# GPSDO_GPS.net
KiCad netlist of a schematic drawn in Altium Designer
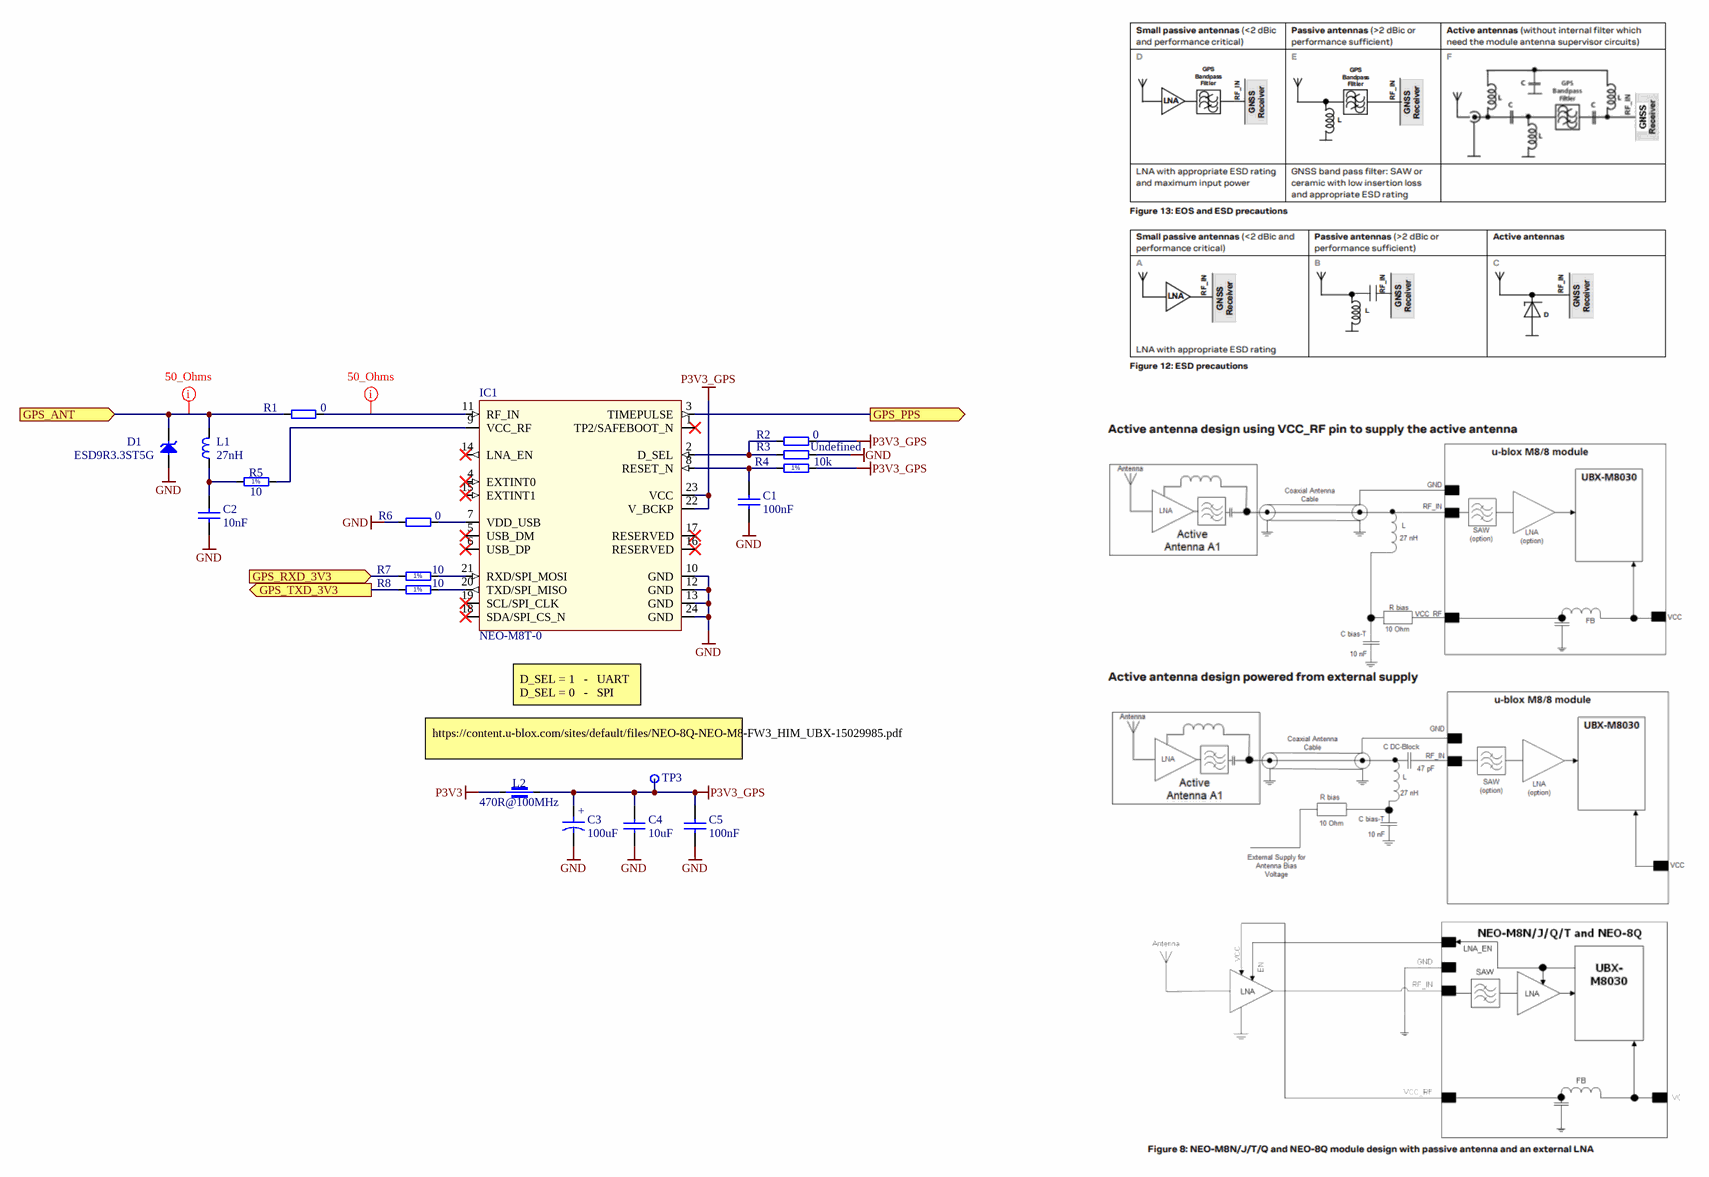
[diagram p0: GPSDO_GPS.SchDoc]

(export (version "E")
  (design (tool "Eeschema 10.0.6"))
  (components
    (comp (ref "C1")
      (value "100nF")
      (footprint "CAPC1005X55N")
      (description "Non-polarised capacitor")
      (fields
        (field (name "PART NUMBER") "CC0402_100NF_16V_10%_X5R")
        (field (name "VOLTAGE") "16V")
        (field (name "AUTHOR") "CERN DEM JLC")
      )
      (libsource (lib "Capacitors") (part "Capacitor - non polarized"))
    )
    (comp (ref "C2")
      (value "10nF")
      (footprint "CAPC1005X55N")
      (description "Non-polarised capacitor")
      (fields
        (field (name "PART NUMBER") "CC0402_10NF_50V_10%_X7R")
        (field (name "VOLTAGE") "50V")
        (field (name "AUTHOR") "CERN DEM MR")
      )
      (libsource (lib "Capacitors") (part "Capacitor - non polarized"))
    )
    (comp (ref "C3")
      (value "100uF")
      (footprint "CAPMP7343X310N")
      (description "Polarised capacitor")
      (fields
        (field (name "PART NUMBER") "CTE7343-31_100UF_20V_10%")
        (field (name "VOLTAGE") "20V")
        (field (name "AUTHOR") "CERN DEM JLC")
      )
      (libsource (lib "Capacitors") (part "Capacitor - polarized"))
    )
    (comp (ref "C4")
      (value "10uF")
      (footprint "CAPC1608X80N")
      (description "Non-polarised capacitor")
      (fields
        (field (name "PART NUMBER") "CC0603_10UF_10V_10%_X5R")
        (field (name "VOLTAGE") "10V")
        (field (name "AUTHOR") "CERN DEM JLC")
      )
      (libsource (lib "Capacitors") (part "Capacitor - non polarized"))
    )
    (comp (ref "C5")
      (value "100nF")
      (footprint "CAPC1005X55N")
      (description "Non-polarised capacitor")
      (fields
        (field (name "PART NUMBER") "CC0402_100NF_16V_10%_X5R")
        (field (name "VOLTAGE") "16V")
        (field (name "AUTHOR") "CERN DEM JLC")
      )
      (libsource (lib "Capacitors") (part "Capacitor - non polarized"))
    )
    (comp (ref "D1")
      (value "ESD9R3.3ST5G")
      (footprint "SOD923")
      (description "Transient Voltage Suppressor Diode (Uni-Directional)")
      (fields (field (name "MANUFACTURER") "ONSEMI"))
      (libsource (lib "Lib") (part "ESD9R3.3ST5G"))
    )
    (comp (ref "IC1")
      (value "NEO-M8T-0")
      (footprint "NEO-M8T_UBL")
      (description "No Description Available")
      (fields (field (name "MANUFACTURER") "Ublox"))
      (libsource (lib "NEO-M8T-0") (part "NEO-M8T-0"))
    )
    (comp (ref "L1")
      (value "27nH")
      (footprint "INDC0402X60N")
      (description "SMD Inductor")
      (fields
        (field (name "MANUFACTURER") "Murata")
        (field (name "MANUFACTURER PART NUMBER") "LQG15HS27NH02D")
      )
      (libsource (lib "Lib") (part "IND_27NH"))
    )
    (comp (ref "L2")
      (value "470R@100MHz")
      (footprint "INDC1608X95N")
      (fields
        (field (name "PART NUMBER") "IND0603_MURATA_BLM18PG471SN1D")
        (field (name "POWER") "1A")
        (field (name "TOLERANCE") "±25%")
        (field (name "AUTHOR") "CERN DEM BC")
      )
      (libsource (lib "Inductors & Transformers") (part "Ferrite Bead"))
    )
    (comp (ref "R1")
      (value "0")
      (footprint "RESC1005X40N")
      (description "Resistor")
      (fields
        (field (name "PART NUMBER") "R0402_0R_JUMPER")
        (field (name "MANUFACTURER") "GENERIC")
        (field (name "AUTHOR") "CERN DEM JLC")
      )
      (libsource (lib "Resistors") (part "Resistor"))
    )
    (comp (ref "R2")
      (value "0")
      (footprint "RESC1005X40N")
      (description "Resistor")
      (fields
        (field (name "PART NUMBER") "R0402_0R_JUMPER")
        (field (name "MANUFACTURER") "GENERIC")
        (field (name "AUTHOR") "CERN DEM JLC")
      )
      (libsource (lib "Resistors") (part "Resistor"))
    )
    (comp (ref "R3")
      (value "Undefined")
      (footprint "RESC1005X40N")
      (description "Resistor")
      (fields (field (name "PART NUMBER") "R0402_NO-VALUE") (field (name "AUTHOR") "CERN DEM JLC"))
      (libsource (lib "Resistors") (part "Resistor"))
    )
    (comp (ref "R4")
      (value "10k")
      (footprint "RESC1005X40N")
      (description "Resistor - 1%")
      (fields
        (field (name "PART NUMBER") "R0402_10K_1%_0.0625W_100PPM")
        (field (name "POWER") "0.0625W")
        (field (name "AUTHOR") "CERN DEM JLC")
      )
      (libsource (lib "Resistors") (part "Resistor - 1%"))
    )
    (comp (ref "R5")
      (value "10")
      (footprint "RESC3216X65N")
      (description "Resistor - 1%")
      (fields
        (field (name "PART NUMBER") "R1206_10R_1%_0.25W_200PPM")
        (field (name "POWER") "0.25W")
        (field (name "AUTHOR") "CERN DEM JLC")
      )
      (libsource (lib "Resistors") (part "Resistor - 1%"))
    )
    (comp (ref "R6")
      (value "0")
      (footprint "RESC1005X40N")
      (description "Resistor")
      (fields
        (field (name "PART NUMBER") "R0402_0R_JUMPER")
        (field (name "MANUFACTURER") "GENERIC")
        (field (name "AUTHOR") "CERN DEM JLC")
      )
      (libsource (lib "Resistors") (part "Resistor"))
    )
    (comp (ref "R7")
      (value "10")
      (footprint "RESC1005X40N")
      (description "Resistor - 1%")
      (fields
        (field (name "PART NUMBER") "R0402_10R_1%_0.0625W_200PPM")
        (field (name "POWER") "0.0625W")
        (field (name "AUTHOR") "CERN DEM JLC")
      )
      (libsource (lib "Resistors") (part "Resistor - 1%"))
    )
    (comp (ref "R8")
      (value "10")
      (footprint "RESC1005X40N")
      (description "Resistor - 1%")
      (fields
        (field (name "PART NUMBER") "R0402_10R_1%_0.0625W_200PPM")
        (field (name "POWER") "0.0625W")
        (field (name "AUTHOR") "CERN DEM JLC")
      )
      (libsource (lib "Resistors") (part "Resistor - 1%"))
    )
    (comp (ref "TP3")
      (value "Test Point")
      (footprint "TPS127")
      (fields (field (name "PART NUMBER") "SMD_PAD_1.27X1.27MM") (field (name "AUTHOR") "CERN DEM JLC"))
      (libsource (lib "Eletro-mechanical") (part "Test Point"))
    )
  )
  (nets
    (net (code "1") (name "/GPS_ANT") (class "Default")
      (node (ref "D1") (pin "1") (pinfunction "C_1") (pintype "passive"))
      (node (ref "L1") (pin "2") (pinfunction "2_2") (pintype "passive"))
      (node (ref "R1") (pin "1") (pinfunction "1_1") (pintype "passive"))
    )
    (net (code "2") (name "/GPS_PPS") (class "Default")
      (node (ref "IC1") (pin "3") (pinfunction "TIMEPULSE_3") (pintype "output"))
    )
    (net (code "3") (name "/GPS_RXD_3V3") (class "Default")
      (node (ref "R7") (pin "1") (pinfunction "1_1") (pintype "passive"))
    )
    (net (code "4") (name "/GPS_TXD_3V3") (class "Default")
      (node (ref "R8") (pin "1") (pinfunction "1_1") (pintype "passive"))
    )
    (net (code "5") (name "GND") (class "Default")
      (node (ref "C1") (pin "1") (pinfunction "1_1") (pintype "passive"))
      (node (ref "C2") (pin "1") (pinfunction "1_1") (pintype "passive"))
      (node (ref "C3") (pin "2") (pinfunction "2_2") (pintype "passive"))
      (node (ref "C4") (pin "1") (pinfunction "1_1") (pintype "passive"))
      (node (ref "C5") (pin "1") (pinfunction "1_1") (pintype "passive"))
      (node (ref "D1") (pin "2") (pinfunction "A_2") (pintype "passive"))
      (node (ref "IC1") (pin "10") (pinfunction "GND_10") (pintype "power_in"))
      (node (ref "IC1") (pin "12") (pinfunction "GND_12") (pintype "power_in"))
      (node (ref "IC1") (pin "13") (pinfunction "GND_13") (pintype "power_in"))
      (node (ref "IC1") (pin "24") (pinfunction "GND_24") (pintype "power_in"))
      (node (ref "R3") (pin "2") (pinfunction "2_2") (pintype "passive"))
      (node (ref "R6") (pin "1") (pinfunction "1_1") (pintype "passive"))
    )
    (net (code "6") (name "Net-(C2-Pad2)") (class "Default")
      (node (ref "C2") (pin "2") (pinfunction "2_2") (pintype "passive"))
      (node (ref "L1") (pin "1") (pinfunction "1_1") (pintype "passive"))
      (node (ref "R5") (pin "1") (pinfunction "1_1") (pintype "passive"))
    )
    (net (code "7") (name "Net-(IC1-D_SEL)") (class "Default")
      (node (ref "IC1") (pin "2") (pinfunction "D_SEL_2") (pintype "input"))
      (node (ref "R2") (pin "1") (pinfunction "1_1") (pintype "passive"))
      (node (ref "R3") (pin "1") (pinfunction "1_1") (pintype "passive"))
    )
    (net (code "8") (name "Net-(IC1-RESET_N)") (class "Default")
      (node (ref "C1") (pin "2") (pinfunction "2_2") (pintype "passive"))
      (node (ref "IC1") (pin "8") (pinfunction "RESET_N_8") (pintype "input"))
      (node (ref "R4") (pin "1") (pinfunction "1_1") (pintype "passive"))
    )
    (net (code "9") (name "Net-(IC1-RF_IN)") (class "Default")
      (node (ref "IC1") (pin "11") (pinfunction "RF_IN_11") (pintype "input"))
      (node (ref "R1") (pin "2") (pinfunction "2_2") (pintype "passive"))
    )
    (net (code "10") (name "Net-(IC1-RXD{slash}SPI_MOSI)") (class "Default")
      (node (ref "IC1") (pin "21") (pinfunction "RXD/SPI_MOSI_21") (pintype "input"))
      (node (ref "R7") (pin "2") (pinfunction "2_2") (pintype "passive"))
    )
    (net (code "11") (name "Net-(IC1-TXD{slash}SPI_MISO)") (class "Default")
      (node (ref "IC1") (pin "20") (pinfunction "TXD/SPI_MISO_20") (pintype "output"))
      (node (ref "R8") (pin "2") (pinfunction "2_2") (pintype "passive"))
    )
    (net (code "12") (name "Net-(IC1-VCC_RF)") (class "Default")
      (node (ref "IC1") (pin "9") (pinfunction "VCC_RF_9") (pintype "power_in"))
      (node (ref "R5") (pin "2") (pinfunction "2_2") (pintype "passive"))
    )
    (net (code "13") (name "Net-(IC1-VDD_USB)") (class "Default")
      (node (ref "IC1") (pin "7") (pinfunction "VDD_USB_7") (pintype "power_in"))
      (node (ref "R6") (pin "2") (pinfunction "2_2") (pintype "passive"))
    )
    (net (code "14") (name "P3V3") (class "Default")
      (node (ref "L2") (pin "1") (pinfunction "1_1") (pintype "passive"))
    )
    (net (code "15") (name "P3V3_GPS") (class "Default")
      (node (ref "C3") (pin "1") (pinfunction "1_1") (pintype "passive"))
      (node (ref "C4") (pin "2") (pinfunction "2_2") (pintype "passive"))
      (node (ref "C5") (pin "2") (pinfunction "2_2") (pintype "passive"))
      (node (ref "IC1") (pin "22") (pinfunction "V_BCKP_22") (pintype "power_in"))
      (node (ref "IC1") (pin "23") (pinfunction "VCC_23") (pintype "power_in"))
      (node (ref "L2") (pin "2") (pinfunction "2_2") (pintype "passive"))
      (node (ref "R2") (pin "2") (pinfunction "2_2") (pintype "passive"))
      (node (ref "R4") (pin "2") (pinfunction "2_2") (pintype "passive"))
      (node (ref "TP3") (pin "1") (pinfunction "1_1") (pintype "bidirectional"))
    )
    (net (code "16") (name "unconnected-(IC1-EXTINT0-Pad4)") (class "Default")
      (node (ref "IC1") (pin "4") (pinfunction "EXTINT0_4") (pintype "input+no_connect"))
    )
    (net (code "17") (name "unconnected-(IC1-EXTINT1-Pad15)") (class "Default")
      (node (ref "IC1") (pin "15") (pinfunction "EXTINT1_15") (pintype "input+no_connect"))
    )
    (net (code "18") (name "unconnected-(IC1-LNA_EN-Pad14)") (class "Default")
      (node (ref "IC1") (pin "14") (pinfunction "LNA_EN_14") (pintype "output+no_connect"))
    )
    (net (code "19") (name "unconnected-(IC1-RESERVED-Pad16)") (class "Default")
      (node (ref "IC1") (pin "16") (pinfunction "RESERVED_16") (pintype "passive+no_connect"))
    )
    (net (code "20") (name "unconnected-(IC1-RESERVED-Pad17)") (class "Default")
      (node (ref "IC1") (pin "17") (pinfunction "RESERVED_17") (pintype "passive+no_connect"))
    )
    (net (code "21") (name "unconnected-(IC1-SCL{slash}SPI_CLK-Pad19)") (class "Default")
      (node (ref "IC1") (pin "19") (pinfunction "SCL/SPI_CLK_19") (pintype "bidirectional+no_connect"))
    )
    (net (code "22") (name "unconnected-(IC1-SDA{slash}SPI_CS_N-Pad18)") (class "Default")
      (node (ref "IC1") (pin "18") (pinfunction "SDA/SPI_CS_N_18") (pintype "bidirectional+no_connect"))
    )
    (net (code "23") (name "unconnected-(IC1-TP2{slash}SAFEBOOT_N-Pad1)") (class "Default")
      (node (ref "IC1") (pin "1") (pinfunction "TP2/SAFEBOOT_N_1") (pintype "bidirectional+no_connect"))
    )
    (net (code "24") (name "unconnected-(IC1-USB_DM-Pad5)") (class "Default")
      (node (ref "IC1") (pin "5") (pinfunction "USB_DM_5") (pintype "bidirectional+no_connect"))
    )
    (net (code "25") (name "unconnected-(IC1-USB_DP-Pad6)") (class "Default")
      (node (ref "IC1") (pin "6") (pinfunction "USB_DP_6") (pintype "bidirectional+no_connect"))
    )
  )
)
